# POWER.net
KiCad netlist of a schematic drawn in Altium Designer
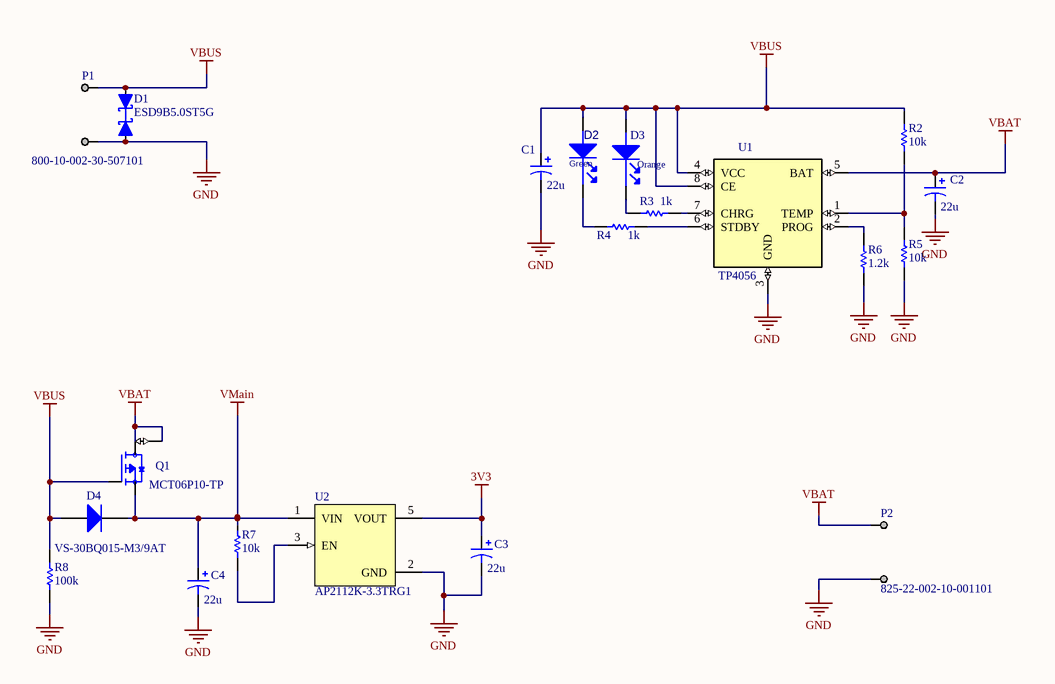
[diagram p0: POWER.SchDoc]

(export (version "E")
  (design (tool "Eeschema 10.0.6"))
  (components
    (comp (ref "C1")
      (value "22u")
      (footprint "CAPPRD250W50D630H1120B")
      (description "CAP ALUM 220UF 20% 160V RADIAL")
      (fields
        (field (name "MANUFACTURER") "Nichicon")
        (field (name "MANUFACTURER PART NUMBER") "UCS2C221MHD1TN")
      )
      (libsource (lib "FAMIS") (part "UCS2C221MHD1TN"))
    )
    (comp (ref "C2")
      (value "22u")
      (footprint "CAPPRD250W50D630H1120B")
      (description "CAP ALUM 220UF 20% 160V RADIAL")
      (fields
        (field (name "MANUFACTURER") "Nichicon")
        (field (name "MANUFACTURER PART NUMBER") "UCS2C221MHD1TN")
      )
      (libsource (lib "FAMIS") (part "UCS2C221MHD1TN"))
    )
    (comp (ref "C3")
      (value "22u")
      (footprint "CAPPRD250W50D630H1120B")
      (description "CAP ALUM 220UF 20% 160V RADIAL")
      (fields
        (field (name "MANUFACTURER") "Nichicon")
        (field (name "MANUFACTURER PART NUMBER") "UCS2C221MHD1TN")
      )
      (libsource (lib "FAMIS") (part "UCS2C221MHD1TN"))
    )
    (comp (ref "C4")
      (value "22u")
      (footprint "CAPPRD250W50D630H1120B")
      (description "CAP ALUM 220UF 20% 160V RADIAL")
      (fields
        (field (name "MANUFACTURER") "Nichicon")
        (field (name "MANUFACTURER PART NUMBER") "UCS2C221MHD1TN")
      )
      (libsource (lib "FAMIS") (part "UCS2C221MHD1TN"))
    )
    (comp (ref "D1")
      (value "ESD9B5.0ST5G")
      (footprint "ESD9B5.0ST5G")
      (description "TVS DIODE 5V SOD923")
      (libsource (lib "FAMIS") (part "ESD9B5.0ST5G"))
    )
    (comp (ref "D2")
      (value "Green")
      (footprint "LED_0603")
      (description "LED SMARTLED GREEN 570NM 0603")
      (fields
        (field (name "MANUFACTURER") "OSRAM Opto Semiconductors Inc")
        (field (name "MANUFACTURER PART NUMBER") "LG L29K-G2J1-24-Z")
      )
      (libsource (lib "FAMIS") (part "LG L29K-G2J1-24-Z"))
    )
    (comp (ref "D3")
      (value "Orange")
      (footprint "LED_0603")
      (description "LED SMARTLED ORANGE 606NM 0603")
      (fields
        (field (name "MANUFACTURER") "OSRAM Opto Semiconductors Inc")
        (field (name "MANUFACTURER PART NUMBER") "LO L29K-H2K1-24-Z")
      )
      (libsource (lib "FAMIS") (part "LO L29K-H2K1-24-Z"))
    )
    (comp (ref "D4")
      (value "VS-30BQ015-M3/9AT")
      (footprint "DO-214AB (SMC)")
      (description "Diode Schottky Rectifier 25V 3A 2-Pin DO-214AB Plastic T/R")
      (fields (field (name "MANUFACTURER") "Vishay Semiconductors"))
      (libsource (lib "FAMIS") (part "VS-30BQ015-M3/9AT"))
    )
    (comp (ref "P1")
      (value "800-10-002-30-507101")
      (footprint "800-10-002-30-507101")
      (description "2 Position Spring Mating Target Connector Surface Mount")
      (libsource (lib "FAMIS") (part "800-10-002-30-507101"))
    )
    (comp (ref "P2")
      (value "825-22-002-10-001101")
      (footprint "825-22-002-10-001101")
      (description "2 Position Spring Piston Connector Through Hole")
      (libsource (lib "FAMIS") (part "825-22-002-10-001101"))
    )
    (comp (ref "Q1")
      (value "MCT06P10-TP")
      (footprint "SOT223")
      (description "P-channel MOSFETSOT-223")
      (fields (field (name "MANUFACTURER") "MCC"))
      (libsource (lib "FAMIS") (part "MCT06P10-TP"))
    )
    (comp (ref "R2")
      (value "10k")
      (footprint "R0805")
      (description "RES SMD 1K OHM 1% 1/8W 0805")
      (fields
        (field (name "MANUFACTURER") "Yageo")
        (field (name "MANUFACTURER PART NUMBER") "RC0805FR-071KL")
        (field (name ".CREATOR") "MM")
        (field (name ".CHECKED PCB") "RF")
        (field (name ".CHECKED SCH") "RF")
      )
      (libsource (lib "FAMIS") (part "RC0805FR-071KL"))
    )
    (comp (ref "R3")
      (value "1k")
      (footprint "R0805")
      (description "RES SMD 1K OHM 1% 1/8W 0805")
      (fields
        (field (name "MANUFACTURER") "Yageo")
        (field (name "MANUFACTURER PART NUMBER") "RC0805FR-071KL")
        (field (name ".CREATOR") "MM")
        (field (name ".CHECKED PCB") "RF")
        (field (name ".CHECKED SCH") "RF")
      )
      (libsource (lib "FAMIS") (part "RC0805FR-071KL"))
    )
    (comp (ref "R4")
      (value "1k")
      (footprint "R0805")
      (description "RES SMD 1K OHM 1% 1/8W 0805")
      (fields
        (field (name "MANUFACTURER") "Yageo")
        (field (name "MANUFACTURER PART NUMBER") "RC0805FR-071KL")
        (field (name ".CREATOR") "MM")
        (field (name ".CHECKED PCB") "RF")
        (field (name ".CHECKED SCH") "RF")
      )
      (libsource (lib "FAMIS") (part "RC0805FR-071KL"))
    )
    (comp (ref "R5")
      (value "10k")
      (footprint "R0805")
      (description "RES SMD 1K OHM 1% 1/8W 0805")
      (fields
        (field (name "MANUFACTURER") "Yageo")
        (field (name "MANUFACTURER PART NUMBER") "RC0805FR-071KL")
        (field (name ".CREATOR") "MM")
        (field (name ".CHECKED PCB") "RF")
        (field (name ".CHECKED SCH") "RF")
      )
      (libsource (lib "FAMIS") (part "RC0805FR-071KL"))
    )
    (comp (ref "R6")
      (value "1.2k")
      (footprint "R0805")
      (description "RES SMD 1K OHM 1% 1/8W 0805")
      (fields
        (field (name "MANUFACTURER") "Yageo")
        (field (name "MANUFACTURER PART NUMBER") "RC0805FR-071KL")
        (field (name ".CREATOR") "MM")
        (field (name ".CHECKED PCB") "RF")
        (field (name ".CHECKED SCH") "RF")
      )
      (libsource (lib "FAMIS") (part "RC0805FR-071KL"))
    )
    (comp (ref "R7")
      (value "10k")
      (footprint "R0805")
      (description "RES SMD 1K OHM 1% 1/8W 0805")
      (fields
        (field (name "MANUFACTURER") "Yageo")
        (field (name "MANUFACTURER PART NUMBER") "RC0805FR-071KL")
        (field (name ".CREATOR") "MM")
        (field (name ".CHECKED PCB") "RF")
        (field (name ".CHECKED SCH") "RF")
      )
      (libsource (lib "FAMIS") (part "RC0805FR-071KL"))
    )
    (comp (ref "R8")
      (value "100k")
      (footprint "R0805")
      (description "RES SMD 1K OHM 1% 1/8W 0805")
      (fields
        (field (name "MANUFACTURER") "Yageo")
        (field (name "MANUFACTURER PART NUMBER") "RC0805FR-071KL")
        (field (name ".CREATOR") "MM")
        (field (name ".CHECKED PCB") "RF")
        (field (name ".CHECKED SCH") "RF")
      )
      (libsource (lib "FAMIS") (part "RC0805FR-071KL"))
    )
    (comp (ref "U1") (value "TP4056") (footprint "SOP-8") (libsource (lib "FAMIS") (part "TP4056")))
    (comp (ref "U2")
      (value "AP2112K-3.3TRG1")
      (footprint "SOT95P285X140-5N")
      (description "IC REG LINEAR 3.3V 600MA SOT25")
      (fields (field (name "MANUFACTURER") "Diodes"))
      (libsource (lib "FAMIS") (part "AP2112K-3.3TRG1"))
    )
  )
  (nets
    (net (code "1") (name "3V3") (class "Default")
      (node (ref "C3") (pin "1") (pinfunction "1_1") (pintype "passive"))
      (node (ref "U2") (pin "5") (pinfunction "VOUT_5") (pintype "power_in"))
    )
    (net (code "2") (name "GND") (class "Default")
      (node (ref "C1") (pin "2") (pinfunction "2_2") (pintype "passive"))
      (node (ref "C2") (pin "2") (pinfunction "2_2") (pintype "passive"))
      (node (ref "C3") (pin "2") (pinfunction "2_2") (pintype "passive"))
      (node (ref "C4") (pin "2") (pinfunction "2_2") (pintype "passive"))
      (node (ref "D1") (pin "1") (pinfunction "1_1") (pintype "passive"))
      (node (ref "P1") (pin "2") (pinfunction "2_2") (pintype "passive"))
      (node (ref "P2") (pin "1") (pinfunction "1_1") (pintype "passive"))
      (node (ref "R5") (pin "1") (pinfunction "1_1") (pintype "passive"))
      (node (ref "R6") (pin "1") (pinfunction "1_1") (pintype "passive"))
      (node (ref "R8") (pin "1") (pinfunction "1_1") (pintype "passive"))
      (node (ref "U1") (pin "3") (pinfunction "GND_3") (pintype "bidirectional"))
      (node (ref "U2") (pin "2") (pinfunction "GND_2") (pintype "power_in"))
    )
    (net (code "3") (name "Net-(D2-cathode)") (class "Default")
      (node (ref "D2") (pin "1") (pinfunction "cathode_1") (pintype "passive"))
      (node (ref "R4") (pin "2") (pinfunction "2_2") (pintype "passive"))
    )
    (net (code "4") (name "Net-(D3-cathode)") (class "Default")
      (node (ref "D3") (pin "1") (pinfunction "cathode_1") (pintype "passive"))
      (node (ref "R3") (pin "2") (pinfunction "2_2") (pintype "passive"))
    )
    (net (code "5") (name "Net-(U1-CHRG)") (class "Default")
      (node (ref "R3") (pin "1") (pinfunction "1_1") (pintype "passive"))
      (node (ref "U1") (pin "7") (pinfunction "CHRG_7") (pintype "bidirectional"))
    )
    (net (code "6") (name "Net-(U1-PROG)") (class "Default")
      (node (ref "R6") (pin "2") (pinfunction "2_2") (pintype "passive"))
      (node (ref "U1") (pin "2") (pinfunction "PROG_2") (pintype "bidirectional"))
    )
    (net (code "7") (name "Net-(U1-STDBY)") (class "Default")
      (node (ref "R4") (pin "1") (pinfunction "1_1") (pintype "passive"))
      (node (ref "U1") (pin "6") (pinfunction "STDBY_6") (pintype "bidirectional"))
    )
    (net (code "8") (name "Net-(U1-TEMP)") (class "Default")
      (node (ref "R2") (pin "1") (pinfunction "1_1") (pintype "passive"))
      (node (ref "R5") (pin "2") (pinfunction "2_2") (pintype "passive"))
      (node (ref "U1") (pin "1") (pinfunction "TEMP_1") (pintype "bidirectional"))
    )
    (net (code "9") (name "Net-(U2-EN)") (class "Default")
      (node (ref "R7") (pin "1") (pinfunction "1_1") (pintype "passive"))
      (node (ref "U2") (pin "3") (pinfunction "EN_3") (pintype "input"))
    )
    (net (code "10") (name "VBAT") (class "Default")
      (node (ref "C2") (pin "1") (pinfunction "1_1") (pintype "passive"))
      (node (ref "P2") (pin "2") (pinfunction "2_2") (pintype "passive"))
      (node (ref "Q1") (pin "2") (pinfunction "D_2") (pintype "passive"))
      (node (ref "Q1") (pin "4") (pinfunction "D2_4") (pintype "bidirectional"))
      (node (ref "U1") (pin "5") (pinfunction "BAT_5") (pintype "bidirectional"))
    )
    (net (code "11") (name "VBUS") (class "Default")
      (node (ref "C1") (pin "1") (pinfunction "1_1") (pintype "passive"))
      (node (ref "D1") (pin "2") (pinfunction "2_2") (pintype "passive"))
      (node (ref "D2") (pin "2") (pinfunction "ANODE_2") (pintype "passive"))
      (node (ref "D3") (pin "2") (pinfunction "ANODE_2") (pintype "passive"))
      (node (ref "D4") (pin "1") (pinfunction "A_1") (pintype "passive"))
      (node (ref "P1") (pin "1") (pinfunction "1_1") (pintype "passive"))
      (node (ref "Q1") (pin "1") (pinfunction "G_1") (pintype "passive"))
      (node (ref "R2") (pin "2") (pinfunction "2_2") (pintype "passive"))
      (node (ref "R8") (pin "2") (pinfunction "2_2") (pintype "passive"))
      (node (ref "U1") (pin "4") (pinfunction "VCC_4") (pintype "bidirectional"))
      (node (ref "U1") (pin "8") (pinfunction "CE_8") (pintype "bidirectional"))
    )
    (net (code "12") (name "VMain") (class "Default")
      (node (ref "C4") (pin "1") (pinfunction "1_1") (pintype "passive"))
      (node (ref "D4") (pin "2") (pinfunction "K_2") (pintype "passive"))
      (node (ref "Q1") (pin "3") (pinfunction "S_3") (pintype "passive"))
      (node (ref "R7") (pin "2") (pinfunction "2_2") (pintype "passive"))
      (node (ref "U2") (pin "1") (pinfunction "VIN_1") (pintype "power_in"))
    )
  )
)
